# WATCHDOG.net
KiCad netlist of a schematic drawn in Altium Designer
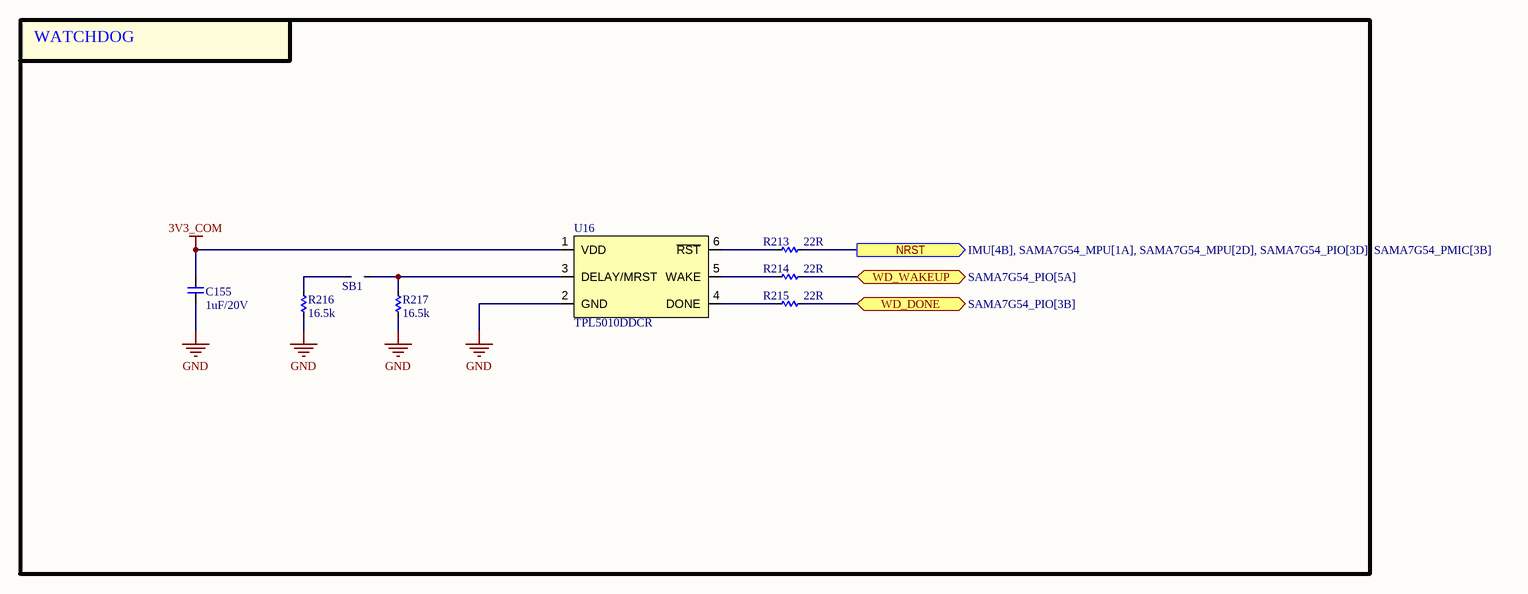
[diagram p0: WATCHDOG.SchDoc]

(export (version "E")
  (design (tool "Eeschema 10.0.6"))
  (components
    (comp (ref "C155")
      (value "1uF/20V")
      (footprint "CAP_C_1005X50_L")
      (description "CAP CHIP")
      (libsource (lib "IFBschelib") (part "_CAP_C_2"))
    )
    (comp (ref "R213")
      (value "22R")
      (footprint "RES_C_1005x30_L")
      (description "RES")
      (libsource (lib "LABLIB") (part "_RES_B_2"))
    )
    (comp (ref "R214")
      (value "22R")
      (footprint "RES_C_1005x30_L")
      (description "RES")
      (libsource (lib "LABLIB") (part "_RES_B_2"))
    )
    (comp (ref "R215")
      (value "22R")
      (footprint "RES_C_1005x30_L")
      (description "RES")
      (libsource (lib "LABLIB") (part "_RES_B_2"))
    )
    (comp (ref "R216")
      (value "16.5k")
      (footprint "RES_C_1005x30_L")
      (description "RES")
      (libsource (lib "IFBschelib") (part "_RES_B_2"))
    )
    (comp (ref "R217")
      (value "16.5k")
      (footprint "RES_C_1005x30_L")
      (description "RES")
      (libsource (lib "IFBschelib") (part "_RES_B_2"))
    )
    (comp (ref "SB1")
      (value "JUMPER")
      (footprint "JUMPER_1608")
      (libsource (lib "IFBschelib") (part "JUMPER"))
    )
    (comp (ref "U16")
      (value "TPL5010DDCR")
      (footprint "TPL5010DDCR")
      (description "OSC PROG TIMER TSOT23-6")
      (libsource (lib "IFBschelib") (part "TPL5010DDCR"))
    )
  )
  (nets
    (net (code "1") (name "/NRST") (class "Default")
      (node (ref "R213") (pin "2") (pinfunction "2_2") (pintype "passive"))
    )
    (net (code "2") (name "/WD_DONE") (class "Default")
      (node (ref "R215") (pin "2") (pinfunction "2_2") (pintype "passive"))
    )
    (net (code "3") (name "/WD_WAKEUP") (class "Default")
      (node (ref "R214") (pin "2") (pinfunction "2_2") (pintype "passive"))
    )
    (net (code "4") (name "3V3_COM") (class "Default")
      (node (ref "C155") (pin "2") (pinfunction "2_2") (pintype "passive"))
      (node (ref "U16") (pin "1") (pinfunction "VDD_1") (pintype "passive"))
    )
    (net (code "5") (name "GND") (class "Default")
      (node (ref "C155") (pin "1") (pinfunction "1_1") (pintype "passive"))
      (node (ref "R216") (pin "2") (pinfunction "2_2") (pintype "passive"))
      (node (ref "R217") (pin "2") (pinfunction "2_2") (pintype "passive"))
      (node (ref "U16") (pin "2") (pinfunction "GND_2") (pintype "passive"))
    )
    (net (code "6") (name "Net-(R216-Pad1)") (class "Default")
      (node (ref "R216") (pin "1") (pinfunction "1_1") (pintype "passive"))
      (node (ref "SB1") (pin "1") (pinfunction "1_1") (pintype "passive"))
    )
    (net (code "7") (name "Net-(U16-DELAY{slash}MRST)") (class "Default")
      (node (ref "R217") (pin "1") (pinfunction "1_1") (pintype "passive"))
      (node (ref "SB1") (pin "2") (pinfunction "2_2") (pintype "passive"))
      (node (ref "U16") (pin "3") (pinfunction "DELAY/MRST_3") (pintype "passive"))
    )
    (net (code "8") (name "Net-(U16-DONE)") (class "Default")
      (node (ref "R215") (pin "1") (pinfunction "1_1") (pintype "passive"))
      (node (ref "U16") (pin "4") (pinfunction "DONE_4") (pintype "passive"))
    )
    (net (code "9") (name "Net-(U16-WAKE)") (class "Default")
      (node (ref "R214") (pin "1") (pinfunction "1_1") (pintype "passive"))
      (node (ref "U16") (pin "5") (pinfunction "WAKE_5") (pintype "passive"))
    )
    (net (code "10") (name "Net-(U16-~{RST})") (class "Default")
      (node (ref "R213") (pin "1") (pinfunction "1_1") (pintype "passive"))
      (node (ref "U16") (pin "6") (pinfunction "~{RST}_6") (pintype "passive"))
    )
  )
)
